# CloudCover.net
KiCad netlist of a schematic drawn in Altium Designer
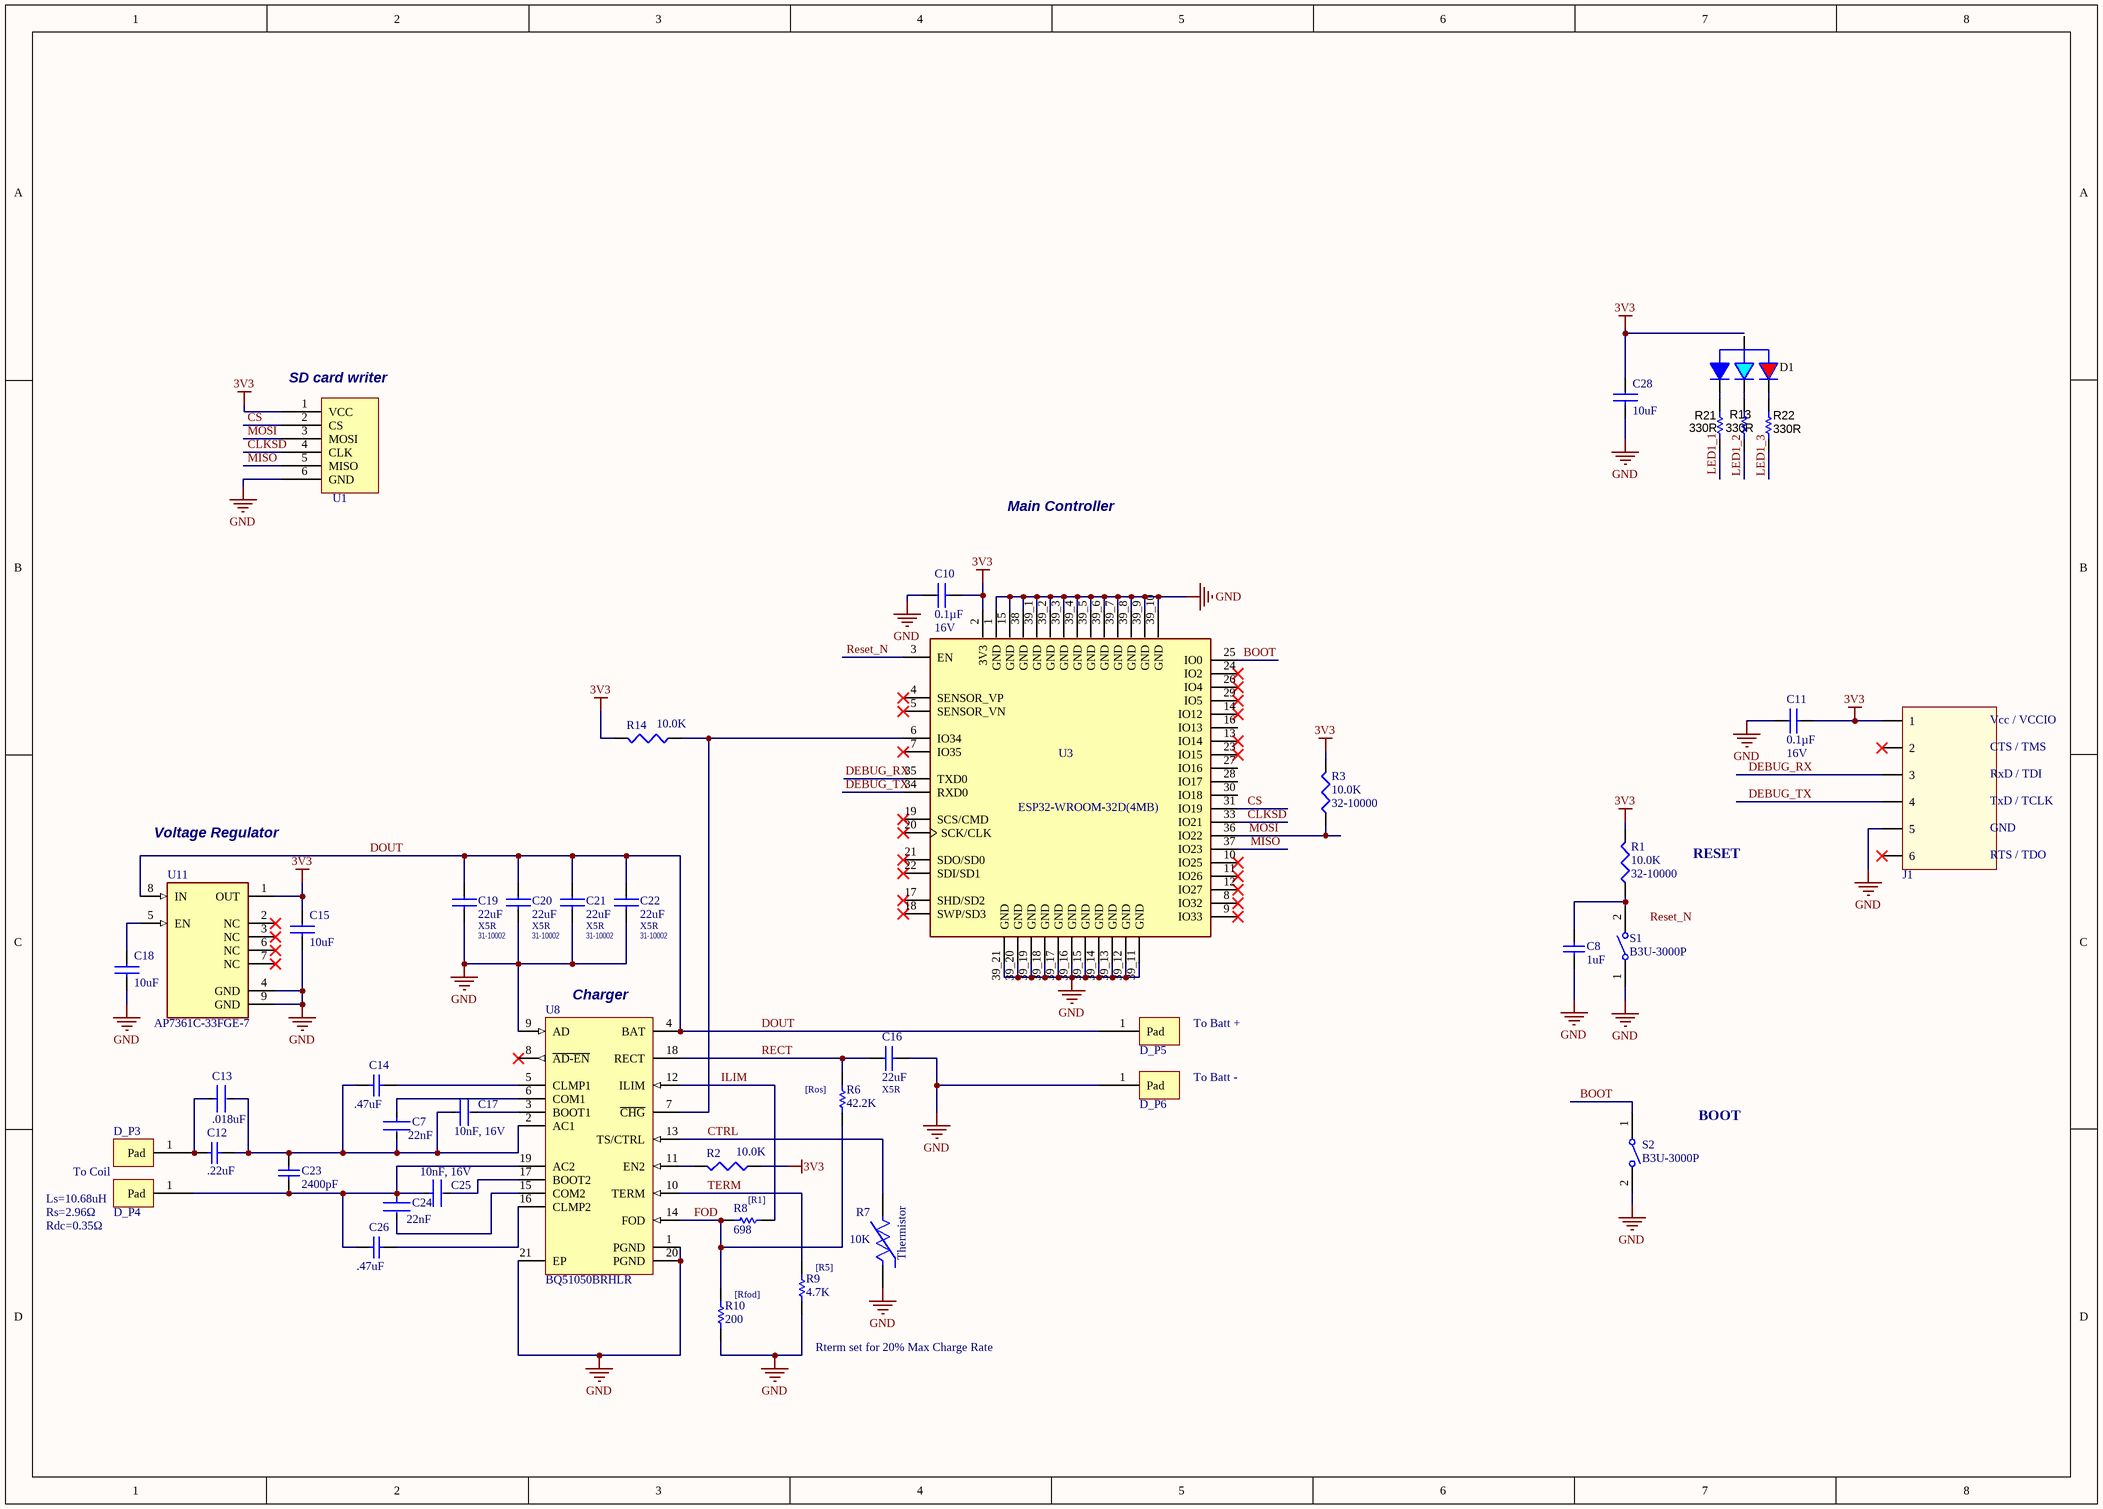
[diagram p0: CloudCover.SchDoc]

(export (version "E")
  (design (tool "Eeschema 10.0.6"))
  (components
    (comp (ref "C7")
      (value "22nF")
      (footprint "FP-CC0402-MFG")
      (description "CC0402KPX7R7BB223 CC0402 22 nF X7R 10.00% 16 V")
      (fields
        (field (name "MANUFACTURER") "YAGEO")
        (field (name "OCTOPART") "https://octopart.com/cc0402kpx7r7bb223-yageo-39266182")
      )
      (libsource (lib "Altium Content Vault") (part "11868f565c42a9108669ba33697ecf6"))
    )
    (comp (ref "C8")
      (value "1uF")
      (footprint "CAPC1005X55X25LL05T10")
      (description "GRM155C80J105KE15D")
      (fields (field (name "MANUFACTURER") "Murata"))
      (libsource (lib "Altium Content Vault") (part "CAP"))
    )
    (comp (ref "C10")
      (value "Cap, 0.1uF, 16V, X7R, 0402")
      (footprint "SMC_IPC_0402")
      (description "Capacitor, Ceramic, 0402, X7R, 16V, 0.1uF")
      (fields
        (field (name "TOLERANCE") "±10%")
        (field (name "MANUFACTURER") "Murata Electronics North America")
        (field (name "CAPACITANCE") "0.1µF")
        (field (name "VOLTAGE - RATED") "16V")
      )
      (libsource (lib "Kickr Sch Lib") (part "31-10107"))
    )
    (comp (ref "C11")
      (value "Cap, 0.1uF, 16V, X7R, 0402")
      (footprint "SMC_IPC_0402")
      (description "Capacitor, Ceramic, 0402, X7R, 16V, 0.1uF")
      (fields
        (field (name "TOLERANCE") "±10%")
        (field (name "MANUFACTURER") "Murata Electronics North America")
        (field (name "CAPACITANCE") "0.1µF")
        (field (name "VOLTAGE - RATED") "16V")
      )
      (libsource (lib "Kickr Sch Lib") (part "31-10107"))
    )
    (comp (ref "C12")
      (value ".22uF")
      (footprint "CAPC2013X145X50ML20T25")
      (description "C0805C224J5RACTU")
      (fields (field (name "MANUFACTURER") "Kemet"))
      (libsource (lib "Altium Content Vault") (part "CAP"))
    )
    (comp (ref "C13")
      (value ".018uF")
      (footprint "FP-C0603C-CF-MFG")
      (description "C0603C183J5RAC7867 C0603 18,000 pF X7R 30ppm/°C 5.00% 50 V")
      (fields
        (field (name "MANUFACTURER") "KEMET")
        (field (name "OCTOPART") "https://octopart.com/c0603c183j5rac7867-kemet-1732095")
      )
      (libsource (lib "Altium Content Vault") (part "b4654b650e69147ec39a6b967a45e02"))
    )
    (comp (ref "C14")
      (value ".47uF")
      (footprint "CAPC1005X55X25LL05T10")
      (description "GRM155R60J474KE19D .47uF 0402")
      (fields (field (name "MANUFACTURER") "Murata") (field (name "PART NUMBER") "GRM155R60J474KE19D"))
      (libsource (lib "Altium Content Vault") (part "CAP"))
    )
    (comp (ref "C15")
      (value "10uF")
      (footprint "SMC_0603")
      (description "CAP CER 10UF 16V X6S 0603")
      (fields
        (field (name "MANUFACTURER") "Murata Electronics North America")
        (field (name "MANUFACTURER PART NUMBER") "GRM188C81C106MA73D")
      )
      (libsource (lib "Kickr Sch Lib") (part "31-10103"))
    )
    (comp (ref "C16")
      (value "22uF")
      (footprint "SMC_0805")
      (description "CAP CER 22UF 10V 20% X5R 0805")
      (fields
        (field (name "TOLERANCE") "20%")
        (field (name "MANUFACTURER") "TDK Corporation")
        (field (name "DIELECTRIC") "X5R")
      )
      (libsource (lib "Kickr Sch Lib") (part "31-10002"))
    )
    (comp (ref "C17")
      (value "10nF, 16V")
      (footprint "FP-CC0402-MFG")
      (description "CC0402KRX7R7BB103 CAP CER 10000PF 16V X7R 0402")
      (fields (field (name "MANUFACTURER PART NUMBER") "CC0402KRX7R7BB103") (field (name "TOLERANCE") "0.1"))
      (libsource (lib "Altium Content Vault") (part "11868f565c42a9108669ba33697ecf6"))
    )
    (comp (ref "C18")
      (value "10uF")
      (footprint "SMC_0603")
      (description "CAP CER 10UF 16V X6S 0603")
      (fields
        (field (name "MANUFACTURER") "Murata Electronics North America")
        (field (name "MANUFACTURER PART NUMBER") "GRM188C81C106MA73D")
      )
      (libsource (lib "Kickr Sch Lib") (part "31-10103"))
    )
    (comp (ref "C19")
      (value "22uF")
      (footprint "SMC_0805")
      (description "CAP CER 22UF 10V 20% X5R 0805")
      (fields
        (field (name "TOLERANCE") "20%")
        (field (name "MANUFACTURER") "TDK Corporation")
        (field (name "DIELECTRIC") "X5R")
        (field (name "INNOVOLT PART NUMBER") "31-10002")
      )
      (libsource (lib "Kickr Sch Lib") (part "31-10002"))
    )
    (comp (ref "C20")
      (value "22uF")
      (footprint "SMC_0805")
      (description "CAP CER 22UF 10V 20% X5R 0805")
      (fields
        (field (name "TOLERANCE") "20%")
        (field (name "MANUFACTURER") "TDK Corporation")
        (field (name "DIELECTRIC") "X5R")
        (field (name "INNOVOLT PART NUMBER") "31-10002")
      )
      (libsource (lib "Kickr Sch Lib") (part "31-10002"))
    )
    (comp (ref "C21")
      (value "22uF")
      (footprint "SMC_0805")
      (description "CAP CER 22UF 10V 20% X5R 0805")
      (fields
        (field (name "TOLERANCE") "20%")
        (field (name "MANUFACTURER") "TDK Corporation")
        (field (name "DIELECTRIC") "X5R")
        (field (name "INNOVOLT PART NUMBER") "31-10002")
      )
      (libsource (lib "Kickr Sch Lib") (part "31-10002"))
    )
    (comp (ref "C22")
      (value "22uF")
      (footprint "SMC_0805")
      (description "CAP CER 22UF 10V 20% X5R 0805")
      (fields
        (field (name "TOLERANCE") "20%")
        (field (name "MANUFACTURER") "TDK Corporation")
        (field (name "DIELECTRIC") "X5R")
        (field (name "INNOVOLT PART NUMBER") "31-10002")
      )
      (libsource (lib "Kickr Sch Lib") (part "31-10002"))
    )
    (comp (ref "C23")
      (value "2400pF")
      (footprint "CAPC1608X90X35NL10T15")
      (description "GRM1885C1H242JA01D")
      (fields (field (name "MANUFACTURER") "Murata"))
      (libsource (lib "Altium Content Vault") (part "CAP"))
    )
    (comp (ref "C24")
      (value "22nF")
      (footprint "FP-CC0402-MFG")
      (description "CC0402KPX7R7BB223 CC0402 22 nF X7R 10.00% 16 V")
      (fields
        (field (name "MANUFACTURER") "YAGEO")
        (field (name "OCTOPART") "https://octopart.com/cc0402kpx7r7bb223-yageo-39266182")
      )
      (libsource (lib "Altium Content Vault") (part "11868f565c42a9108669ba33697ecf6"))
    )
    (comp (ref "C25")
      (value "10nF, 16V")
      (footprint "FP-CC0402-MFG")
      (description "CC0402KRX7R7BB103 CAP CER 10000PF 16V X7R 0402")
      (fields (field (name "MANUFACTURER PART NUMBER") "CC0402KRX7R7BB103") (field (name "TOLERANCE") "0.1"))
      (libsource (lib "Altium Content Vault") (part "11868f565c42a9108669ba33697ecf6"))
    )
    (comp (ref "C26")
      (value ".47uF")
      (footprint "CAPC1005X55X25LL05T10")
      (description "GRM155R60J474KE19D .47uF 0402")
      (fields (field (name "MANUFACTURER") "Murata") (field (name "PART NUMBER") "GRM155R60J474KE19D"))
      (libsource (lib "Altium Content Vault") (part "CAP"))
    )
    (comp (ref "C28")
      (value "10uF")
      (footprint "SMC_0603")
      (description "CAP CER 10UF 16V X6S 0603")
      (fields
        (field (name "MANUFACTURER") "Murata Electronics North America")
        (field (name "MANUFACTURER PART NUMBER") "GRM188C81C106MA73D")
      )
      (libsource (lib "Kickr Sch Lib") (part "31-10103"))
    )
    (comp (ref "D1")
      (value "CLMVC-FKC-CGJJM569ABB7A343")
      (footprint "CLMVC-FKC-CGJJM569ABB7A343")
      (description "LED Multicolor Red/Green/Blue 624nm/540nm/470nm 25mA/13mA/13mA 4-Pin Surface Mount T/R")
      (fields (field (name "MANUFACTURER") "Cree"))
      (libsource (lib "FAMIS") (part "CLMVC-FKC-CGJJM569ABB7A343"))
    )
    (comp (ref "D_P3") (value "PAD") (footprint "PAD 2x1.5") (libsource (lib "") (part "PAD_1_1")))
    (comp (ref "D_P4") (value "PAD") (footprint "PAD 2x1.5") (libsource (lib "") (part "PAD_1_1")))
    (comp (ref "D_P5") (value "PAD") (footprint "PAD 2x1.5") (libsource (lib "Kickr Sch Lib") (part "PAD_1")))
    (comp (ref "D_P6") (value "PAD") (footprint "PAD 2x1.5") (libsource (lib "Kickr Sch Lib") (part "PAD_1")))
    (comp (ref "J1")
      (value "TC2030-NL-FTDI TTL-232R USB")
      (footprint "TC2030-MCP - NL")
      (description "Footprint TC2030-CTX Debug Connector")
      (fields (field (name "INNOVOLT PART NUMBER") "40-10067") (field (name "MANUFACTURER") "Tag-Connect"))
      (libsource (lib "SudHub") (part "TC2030-NL"))
    )
    (comp (ref "R1")
      (value "10.0K")
      (footprint "SMR_0402 - Basil")
      (description "RES 10.0K OHM 1/16W 1% 0402 SMD")
      (fields
        (field (name "MANUFACTURER PART NUMBER") "RC0402FR-0710KL")
        (field (name "MANUFACTURER") "Yageo")
        (field (name "INNOVOLT PART NUMBER") "32-10000")
      )
      (libsource (lib "Kickr Sch Lib") (part "32-10000"))
    )
    (comp (ref "R2")
      (value "10.0K")
      (footprint "SMR_0402 - Basil")
      (description "RES 10.0K OHM 1/16W 1% 0402 SMD")
      (fields
        (field (name "MANUFACTURER PART NUMBER") "RC0402FR-0710KL")
        (field (name "MANUFACTURER") "Yageo")
      )
      (libsource (lib "Kickr Sch Lib") (part "32-10000"))
    )
    (comp (ref "R3")
      (value "10.0K")
      (footprint "SMR_0402 - Basil")
      (description "RES 10.0K OHM 1/16W 1% 0402 SMD")
      (fields
        (field (name "MANUFACTURER PART NUMBER") "RC0402FR-0710KL")
        (field (name "MANUFACTURER") "Yageo")
        (field (name "INNOVOLT PART NUMBER") "32-10000")
      )
      (libsource (lib "Kickr Sch Lib") (part "32-10000"))
    )
    (comp (ref "R6")
      (value "42.2K")
      (footprint "RESC1005X40X25NL05T10")
      (description "RC0402FR-0742K2L 42.2K, 1/16W, 0402")
      (fields (field (name "PART NUMBER") "RC0402FR-0742K2L") (field (name "MANUFACTURER") "Yageo / Phycomp"))
      (libsource (lib "Altium Content Vault") (part "RES"))
    )
    (comp (ref "R7")
      (value "10K")
      (footprint "FP-NTCS0805-MFG")
      (description "B57863S0103F040")
      (fields
        (field (name "OCTOPART") "https://octopart.com/ntcs0805e3103jmt-vishay-39723061")
        (field (name "TOLERANCE") "5%")
      )
      (libsource (lib "Altium Content Vault") (part "3b148a6ebabc5fb4d708a66c052d352"))
    )
    (comp (ref "R8")
      (value "698")
      (footprint "RESC1005X40X25ML05T05")
      (description "CRCW0402698RFKED 698 ohm, 1/16W, 0402")
      (fields (field (name "MANUFACTURER") "Vishay Dale") (field (name "PART NUMBER") "CRCW0402698RFKED"))
      (libsource (lib "Altium Content Vault") (part "RES"))
    )
    (comp (ref "R9")
      (value "4.7K")
      (footprint "RESC1005X40X25LL05T05")
      (fields (field (name "TOLERANCE") "1%") (field (name "PARTNUMBER") "ERJ-2RKF4701X"))
      (libsource (lib "Altium Content Vault") (part "RES-2"))
    )
    (comp (ref "R10")
      (value "200")
      (footprint "RESC1005X40X25ML05T10")
      (description "RC0402FR-07200RL 200 ohm, 1/16W, 0402")
      (fields (field (name "MANUFACTURER") "Yageo / Phycomp") (field (name "PART NUMBER") "RC0402FR-07200RL"))
      (libsource (lib "Altium Content Vault") (part "RES"))
    )
    (comp (ref "R13")
      (value "330R")
      (footprint "0402")
      (description "Res Thick Film 0402 330 Ohm 1% 1/16W ±100ppm/°C Molded SMD Paper T/R")
      (fields
        (field (name "MANUFACTURER") "Vishay")
        (field (name "MANUFACTURER PART NUMBER") "CRCW0402330RFKED")
      )
      (libsource (lib "FAMIS") (part "CRCW0402330RFKED"))
    )
    (comp (ref "R14")
      (value "10.0K")
      (footprint "SMR_0402 - Basil")
      (description "RES 10.0K OHM 1/16W 1% 0402 SMD")
      (fields
        (field (name "MANUFACTURER PART NUMBER") "RC0402FR-0710KL")
        (field (name "MANUFACTURER") "Yageo")
      )
      (libsource (lib "Kickr Sch Lib") (part "32-10000"))
    )
    (comp (ref "R21")
      (value "330R")
      (footprint "0402")
      (description "Res Thick Film 0402 330 Ohm 1% 1/16W ±100ppm/°C Molded SMD Paper T/R")
      (fields
        (field (name "MANUFACTURER") "Vishay")
        (field (name "MANUFACTURER PART NUMBER") "CRCW0402330RFKED")
      )
      (libsource (lib "FAMIS") (part "CRCW0402330RFKED"))
    )
    (comp (ref "R22")
      (value "330R")
      (footprint "0402")
      (description "Res Thick Film 0402 330 Ohm 1% 1/16W ±100ppm/°C Molded SMD Paper T/R")
      (fields
        (field (name "MANUFACTURER") "Vishay")
        (field (name "MANUFACTURER PART NUMBER") "CRCW0402330RFKED")
      )
      (libsource (lib "FAMIS") (part "CRCW0402330RFKED"))
    )
    (comp (ref "S1")
      (value "B3U-3000P")
      (footprint "OMRON-B3U-3000P_V")
      (description "Ultra-Small Tactile Switch, 1 to 50 mA, 3 to 12 V, -25 to 70 degC, 2-Pin SMD, RoHS, Tape and Reel")
      (fields (field (name "TOLERANCE") "20%"))
      (libsource (lib "Altium Content Vault") (part "SW-SPST-2_B"))
    )
    (comp (ref "S2")
      (value "B3U-3000P")
      (footprint "OMRON-B3U-3000P_V")
      (description "Ultra-Small Tactile Switch, 1 to 50 mA, 3 to 12 V, -25 to 70 degC, 2-Pin SMD, RoHS, Tape and Reel")
      (fields (field (name "TOLERANCE") "20%"))
      (libsource (lib "Altium Content Vault") (part "SW-SPST-2_B"))
    )
    (comp (ref "U1") (value "SDCARDSLOT") (libsource (lib "FAMIS") (part "SDCARDSLOT")))
    (comp (ref "U3")
      (value "ESP32-WROOM-32D(4MB)")
      (footprint "MODULE_ESP32-WROOM-32D")
      (description "Bluetooth and Wi-Fi Module 2.4GHz to 2.5GHz 2.7V to 3.6V 4MB Flash 38-Pin SMD Module")
      (fields (field (name "MANUFACTURER") "Espressif Systems"))
      (libsource (lib "FAMIS") (part "ESP32-WROOM-32D(4MB)"))
    )
    (comp (ref "U8")
      (value "BQ51050BRHLR")
      (footprint "RHL0020A_V")
      (libsource (lib "Altium Content Vault") (part "TI-BQ51050B_51051B-RHL20"))
    )
    (comp (ref "U11")
      (value "AP7361C-33FGE-7")
      (footprint "FP-U-DFN3030-8_Type_E-MFG")
      (description "IC REG LINEAR 3.3V 1A UDFN3030-8")
      (fields
        (field (name "MANUFACTURER") "Diodes Inc.")
        (field (name "OCTOPART") "https://octopart.com/ap7361c-33fge-7-diodes+inc.-65869522")
      )
      (libsource (lib "Altium Content Vault") (part "2971fe8480f7e8815ea3c3920f93e3e"))
    )
  )
  (nets
    (net (code "1") (name "/BOOT") (class "Default")
      (node (ref "S2") (pin "1") (pinfunction "1_1") (pintype "passive"))
      (node (ref "U3") (pin "25") (pinfunction "IO0_25") (pintype "passive"))
    )
    (net (code "2") (name "/CLKSD") (class "Default")
      (node (ref "U1") (pin "4") (pinfunction "CLK_4") (pintype "passive"))
      (node (ref "U3") (pin "33") (pinfunction "IO21_33") (pintype "passive"))
    )
    (net (code "3") (name "/CS") (class "Default")
      (node (ref "U1") (pin "2") (pinfunction "CS_2") (pintype "passive"))
      (node (ref "U3") (pin "31") (pinfunction "IO19_31") (pintype "passive"))
    )
    (net (code "4") (name "/CTRL") (class "Default")
      (node (ref "R7") (pin "2") (pinfunction "2_2") (pintype "passive"))
      (node (ref "U8") (pin "13") (pinfunction "TS/CTRL_13") (pintype "input"))
    )
    (net (code "5") (name "/DEBUG_RX") (class "Default")
      (node (ref "J1") (pin "3") (pinfunction "3_3") (pintype "passive"))
      (node (ref "U3") (pin "35") (pinfunction "TXD0_35") (pintype "passive"))
    )
    (net (code "6") (name "/DEBUG_TX") (class "Default")
      (node (ref "J1") (pin "4") (pinfunction "4_4") (pintype "passive"))
      (node (ref "U3") (pin "34") (pinfunction "RXD0_34") (pintype "passive"))
    )
    (net (code "7") (name "/DOUT") (class "Default")
      (node (ref "C19") (pin "1") (pinfunction "1_1") (pintype "passive"))
      (node (ref "C20") (pin "1") (pinfunction "1_1") (pintype "passive"))
      (node (ref "C21") (pin "1") (pinfunction "1_1") (pintype "passive"))
      (node (ref "C22") (pin "1") (pinfunction "1_1") (pintype "passive"))
      (node (ref "D_P5") (pin "1") (pinfunction "Pad_1") (pintype "passive"))
      (node (ref "U11") (pin "8") (pinfunction "IN_8") (pintype "input"))
      (node (ref "U8") (pin "4") (pinfunction "BAT_4") (pintype "power_in"))
    )
    (net (code "8") (name "/FOD") (class "Default")
      (node (ref "R10") (pin "2") (pinfunction "2_2") (pintype "passive"))
      (node (ref "R6") (pin "1") (pinfunction "1_1") (pintype "passive"))
      (node (ref "R8") (pin "1") (pinfunction "1_1") (pintype "passive"))
      (node (ref "U8") (pin "14") (pinfunction "FOD_14") (pintype "input"))
    )
    (net (code "9") (name "/ILIM") (class "Default")
      (node (ref "R8") (pin "2") (pinfunction "2_2") (pintype "passive"))
      (node (ref "U8") (pin "12") (pinfunction "ILIM_12") (pintype "input"))
    )
    (net (code "10") (name "/LED1_1") (class "Default")
      (node (ref "R21") (pin "1") (pinfunction "1_1") (pintype "passive"))
    )
    (net (code "11") (name "/LED1_2") (class "Default")
      (node (ref "R13") (pin "1") (pinfunction "1_1") (pintype "passive"))
    )
    (net (code "12") (name "/LED1_3") (class "Default")
      (node (ref "R22") (pin "1") (pinfunction "1_1") (pintype "passive"))
    )
    (net (code "13") (name "/MISO") (class "Default")
      (node (ref "U1") (pin "5") (pinfunction "MISO_5") (pintype "passive"))
      (node (ref "U3") (pin "37") (pinfunction "IO23_37") (pintype "passive"))
    )
    (net (code "14") (name "/MOSI") (class "Default")
      (node (ref "R3") (pin "1") (pinfunction "1_1") (pintype "passive"))
      (node (ref "U1") (pin "3") (pinfunction "MOSI_3") (pintype "passive"))
      (node (ref "U3") (pin "36") (pinfunction "IO22_36") (pintype "passive"))
    )
    (net (code "15") (name "/RECT") (class "Default")
      (node (ref "C16") (pin "1") (pinfunction "1_1") (pintype "passive"))
      (node (ref "R6") (pin "2") (pinfunction "2_2") (pintype "passive"))
      (node (ref "U8") (pin "18") (pinfunction "RECT_18") (pintype "passive"))
    )
    (net (code "16") (name "/Reset_N") (class "Default")
      (node (ref "U3") (pin "3") (pinfunction "EN_3") (pintype "passive"))
    )
    (net (code "17") (name "/TERM") (class "Default")
      (node (ref "R9") (pin "2") (pinfunction "2_2") (pintype "passive"))
      (node (ref "U8") (pin "10") (pinfunction "TERM_10") (pintype "input"))
    )
    (net (code "18") (name "3V3") (class "Default")
      (node (ref "C10") (pin "2") (pinfunction "2_2") (pintype "passive"))
      (node (ref "C11") (pin "2") (pinfunction "2_2") (pintype "passive"))
      (node (ref "C15") (pin "1") (pinfunction "1_1") (pintype "passive"))
      (node (ref "C28") (pin "1") (pinfunction "1_1") (pintype "passive"))
      (node (ref "J1") (pin "1") (pinfunction "1_1") (pintype "passive"))
      (node (ref "R1") (pin "2") (pinfunction "2_2") (pintype "passive"))
      (node (ref "R14") (pin "2") (pinfunction "2_2") (pintype "passive"))
      (node (ref "R2") (pin "1") (pinfunction "1_1") (pintype "passive"))
      (node (ref "R3") (pin "2") (pinfunction "2_2") (pintype "passive"))
      (node (ref "U1") (pin "1") (pinfunction "VCC_1") (pintype "passive"))
      (node (ref "U11") (pin "1") (pinfunction "OUT_1") (pintype "power_in"))
      (node (ref "U3") (pin "2") (pinfunction "3V3_2") (pintype "passive"))
    )
    (net (code "19") (name "GND") (class "Default")
      (node (ref "C10") (pin "1") (pinfunction "1_1") (pintype "passive"))
      (node (ref "C11") (pin "1") (pinfunction "1_1") (pintype "passive"))
      (node (ref "C15") (pin "2") (pinfunction "2_2") (pintype "passive"))
      (node (ref "C16") (pin "2") (pinfunction "2_2") (pintype "passive"))
      (node (ref "C18") (pin "2") (pinfunction "2_2") (pintype "passive"))
      (node (ref "C19") (pin "2") (pinfunction "2_2") (pintype "passive"))
      (node (ref "C20") (pin "2") (pinfunction "2_2") (pintype "passive"))
      (node (ref "C21") (pin "2") (pinfunction "2_2") (pintype "passive"))
      (node (ref "C22") (pin "2") (pinfunction "2_2") (pintype "passive"))
      (node (ref "C28") (pin "2") (pinfunction "2_2") (pintype "passive"))
      (node (ref "C8") (pin "1") (pinfunction "1_1") (pintype "passive"))
      (node (ref "D_P6") (pin "1") (pinfunction "Pad_1") (pintype "passive"))
      (node (ref "J1") (pin "5") (pinfunction "5_5") (pintype "passive"))
      (node (ref "R10") (pin "1") (pinfunction "1_1") (pintype "passive"))
      (node (ref "R7") (pin "1") (pinfunction "1_1") (pintype "passive"))
      (node (ref "R9") (pin "1") (pinfunction "1_1") (pintype "passive"))
      (node (ref "S1") (pin "1") (pinfunction "1_1") (pintype "passive"))
      (node (ref "S2") (pin "2") (pinfunction "2_2") (pintype "passive"))
      (node (ref "U1") (pin "6") (pinfunction "GND_6") (pintype "passive"))
      (node (ref "U11") (pin "4") (pinfunction "GND_4") (pintype "power_in"))
      (node (ref "U11") (pin "9") (pinfunction "GND_9") (pintype "power_in"))
      (node (ref "U3") (pin "1") (pinfunction "GND_1") (pintype "passive"))
      (node (ref "U3") (pin "15") (pinfunction "GND_15") (pintype "passive"))
      (node (ref "U3") (pin "38") (pinfunction "GND_38") (pintype "passive"))
      (node (ref "U3") (pin "39_1") (pinfunction "GND_39_1") (pintype "passive"))
      (node (ref "U3") (pin "39_10") (pinfunction "GND_39_10") (pintype "passive"))
      (node (ref "U3") (pin "39_11") (pinfunction "GND_39_11") (pintype "passive"))
      (node (ref "U3") (pin "39_12") (pinfunction "GND_39_12") (pintype "passive"))
      (node (ref "U3") (pin "39_13") (pinfunction "GND_39_13") (pintype "passive"))
      (node (ref "U3") (pin "39_14") (pinfunction "GND_39_14") (pintype "passive"))
      (node (ref "U3") (pin "39_15") (pinfunction "GND_39_15") (pintype "passive"))
      (node (ref "U3") (pin "39_16") (pinfunction "GND_39_16") (pintype "passive"))
      (node (ref "U3") (pin "39_17") (pinfunction "GND_39_17") (pintype "passive"))
      (node (ref "U3") (pin "39_18") (pinfunction "GND_39_18") (pintype "passive"))
      (node (ref "U3") (pin "39_19") (pinfunction "GND_39_19") (pintype "passive"))
      (node (ref "U3") (pin "39_2") (pinfunction "GND_39_2") (pintype "passive"))
      (node (ref "U3") (pin "39_20") (pinfunction "GND_39_20") (pintype "passive"))
      (node (ref "U3") (pin "39_21") (pinfunction "GND_39_21") (pintype "passive"))
      (node (ref "U3") (pin "39_3") (pinfunction "GND_39_3") (pintype "passive"))
      (node (ref "U3") (pin "39_4") (pinfunction "GND_39_4") (pintype "passive"))
      (node (ref "U3") (pin "39_5") (pinfunction "GND_39_5") (pintype "passive"))
      (node (ref "U3") (pin "39_6") (pinfunction "GND_39_6") (pintype "passive"))
      (node (ref "U3") (pin "39_7") (pinfunction "GND_39_7") (pintype "passive"))
      (node (ref "U3") (pin "39_8") (pinfunction "GND_39_8") (pintype "passive"))
      (node (ref "U3") (pin "39_9") (pinfunction "GND_39_9") (pintype "passive"))
      (node (ref "U8") (pin "1") (pinfunction "PGND_1") (pintype "power_in"))
      (node (ref "U8") (pin "20") (pinfunction "PGND_20") (pintype "power_in"))
      (node (ref "U8") (pin "21") (pinfunction "EP_21") (pintype "passive"))
      (node (ref "U8") (pin "9") (pinfunction "AD_9") (pintype "input"))
    )
    (net (code "20") (name "Net-(C8-Pad2)") (class "Default")
      (node (ref "C8") (pin "2") (pinfunction "2_2") (pintype "passive"))
      (node (ref "R1") (pin "1") (pinfunction "1_1") (pintype "passive"))
      (node (ref "S1") (pin "2") (pinfunction "2_2") (pintype "passive"))
    )
    (net (code "21") (name "Net-(C12-Pad1)") (class "Default")
      (node (ref "C12") (pin "1") (pinfunction "1_1") (pintype "passive"))
      (node (ref "C13") (pin "1") (pinfunction "1_1") (pintype "passive"))
      (node (ref "D_P3") (pin "1") (pinfunction "Pad_1") (pintype "passive"))
    )
    (net (code "22") (name "Net-(D1-K-Pad2)") (class "Default")
      (node (ref "D1") (pin "2") (pinfunction "K_2") (pintype "passive"))
      (node (ref "R21") (pin "2") (pinfunction "2_2") (pintype "passive"))
    )
    (net (code "23") (name "Net-(D1-K-Pad3)") (class "Default")
      (node (ref "D1") (pin "3") (pinfunction "K_3") (pintype "passive"))
      (node (ref "R13") (pin "2") (pinfunction "2_2") (pintype "passive"))
    )
    (net (code "24") (name "Net-(D1-K-Pad4)") (class "Default")
      (node (ref "D1") (pin "4") (pinfunction "K_4") (pintype "passive"))
      (node (ref "R22") (pin "2") (pinfunction "2_2") (pintype "passive"))
    )
    (net (code "25") (name "Net-(U3-IO34)") (class "Default")
      (node (ref "R14") (pin "1") (pinfunction "1_1") (pintype "passive"))
      (node (ref "U3") (pin "6") (pinfunction "IO34_6") (pintype "passive"))
      (node (ref "U8") (pin "7") (pinfunction "~{CHG}_7") (pintype "open_collector"))
    )
    (net (code "26") (name "Net-(U8-AC1)") (class "Default")
      (node (ref "C12") (pin "2") (pinfunction "2_2") (pintype "passive"))
      (node (ref "C13") (pin "2") (pinfunction "2_2") (pintype "passive"))
      (node (ref "C14") (pin "1") (pinfunction "1_1") (pintype "passive"))
      (node (ref "C17") (pin "1") (pinfunction "1_1") (pintype "passive"))
      (node (ref "C23") (pin "2") (pinfunction "2_2") (pintype "passive"))
      (node (ref "C7") (pin "2") (pinfunction "2_2") (pintype "passive"))
      (node (ref "U8") (pin "2") (pinfunction "AC1_2") (pintype "power_in"))
    )
    (net (code "27") (name "Net-(U8-AC2)") (class "Default")
      (node (ref "C23") (pin "1") (pinfunction "1_1") (pintype "passive"))
      (node (ref "C24") (pin "1") (pinfunction "1_1") (pintype "passive"))
      (node (ref "C25") (pin "1") (pinfunction "1_1") (pintype "passive"))
      (node (ref "C26") (pin "1") (pinfunction "1_1") (pintype "passive"))
      (node (ref "D_P4") (pin "1") (pinfunction "Pad_1") (pintype "passive"))
      (node (ref "U8") (pin "19") (pinfunction "AC2_19") (pintype "power_in"))
    )
    (net (code "28") (name "Net-(U8-BOOT1)") (class "Default")
      (node (ref "C17") (pin "2") (pinfunction "2_2") (pintype "passive"))
      (node (ref "U8") (pin "3") (pinfunction "BOOT1_3") (pintype "passive"))
    )
    (net (code "29") (name "Net-(U8-BOOT2)") (class "Default")
      (node (ref "C25") (pin "2") (pinfunction "2_2") (pintype "passive"))
      (node (ref "U8") (pin "17") (pinfunction "BOOT2_17") (pintype "passive"))
    )
    (net (code "30") (name "Net-(U8-CLMP1)") (class "Default")
      (node (ref "C14") (pin "2") (pinfunction "2_2") (pintype "passive"))
      (node (ref "U8") (pin "5") (pinfunction "CLMP1_5") (pintype "open_collector"))
    )
    (net (code "31") (name "Net-(U8-CLMP2)") (class "Default")
      (node (ref "C26") (pin "2") (pinfunction "2_2") (pintype "passive"))
      (node (ref "U8") (pin "16") (pinfunction "CLMP2_16") (pintype "open_collector"))
    )
    (net (code "32") (name "Net-(U8-COM1)") (class "Default")
      (node (ref "C7") (pin "1") (pinfunction "1_1") (pintype "passive"))
      (node (ref "U8") (pin "6") (pinfunction "COM1_6") (pintype "open_collector"))
    )
    (net (code "33") (name "Net-(U8-COM2)") (class "Default")
      (node (ref "C24") (pin "2") (pinfunction "2_2") (pintype "passive"))
      (node (ref "U8") (pin "15") (pinfunction "COM2_15") (pintype "open_collector"))
    )
    (net (code "34") (name "Net-(U8-EN2)") (class "Default")
      (node (ref "R2") (pin "2") (pinfunction "2_2") (pintype "passive"))
      (node (ref "U8") (pin "11") (pinfunction "EN2_11") (pintype "input"))
    )
    (net (code "35") (name "Net-(U11-EN)") (class "Default")
      (node (ref "C18") (pin "1") (pinfunction "1_1") (pintype "passive"))
      (node (ref "U11") (pin "5") (pinfunction "EN_5") (pintype "input"))
    )
    (net (code "36") (name "unconnected-(D1-A-Pad1)") (class "Default")
      (node (ref "D1") (pin "1") (pinfunction "A_1") (pintype "passive"))
    )
    (net (code "37") (name "unconnected-(J1-Pad2)") (class "Default")
      (node (ref "J1") (pin "2") (pinfunction "2_2") (pintype "passive+no_connect"))
    )
    (net (code "38") (name "unconnected-(J1-Pad6)") (class "Default")
      (node (ref "J1") (pin "6") (pinfunction "6_6") (pintype "passive+no_connect"))
    )
    (net (code "39") (name "unconnected-(U3-IO2-Pad24)") (class "Default")
      (node (ref "U3") (pin "24") (pinfunction "IO2_24") (pintype "passive+no_connect"))
    )
    (net (code "40") (name "unconnected-(U3-IO4-Pad26)") (class "Default")
      (node (ref "U3") (pin "26") (pinfunction "IO4_26") (pintype "passive+no_connect"))
    )
    (net (code "41") (name "unconnected-(U3-IO5-Pad29)") (class "Default")
      (node (ref "U3") (pin "29") (pinfunction "IO5_29") (pintype "passive+no_connect"))
    )
    (net (code "42") (name "unconnected-(U3-IO12-Pad14)") (class "Default")
      (node (ref "U3") (pin "14") (pinfunction "IO12_14") (pintype "passive+no_connect"))
    )
    (net (code "43") (name "unconnected-(U3-IO13-Pad16)") (class "Default")
      (node (ref "U3") (pin "16") (pinfunction "IO13_16") (pintype "passive"))
    )
    (net (code "44") (name "unconnected-(U3-IO14-Pad13)") (class "Default")
      (node (ref "U3") (pin "13") (pinfunction "IO14_13") (pintype "passive+no_connect"))
    )
    (net (code "45") (name "unconnected-(U3-IO15-Pad23)") (class "Default")
      (node (ref "U3") (pin "23") (pinfunction "IO15_23") (pintype "passive+no_connect"))
    )
    (net (code "46") (name "unconnected-(U3-IO16-Pad27)") (class "Default")
      (node (ref "U3") (pin "27") (pinfunction "IO16_27") (pintype "passive"))
    )
    (net (code "47") (name "unconnected-(U3-IO17-Pad28)") (class "Default")
      (node (ref "U3") (pin "28") (pinfunction "IO17_28") (pintype "passive"))
    )
    (net (code "48") (name "unconnected-(U3-IO18-Pad30)") (class "Default")
      (node (ref "U3") (pin "30") (pinfunction "IO18_30") (pintype "passive"))
    )
    (net (code "49") (name "unconnected-(U3-IO25-Pad10)") (class "Default")
      (node (ref "U3") (pin "10") (pinfunction "IO25_10") (pintype "passive+no_connect"))
    )
    (net (code "50") (name "unconnected-(U3-IO26-Pad11)") (class "Default")
      (node (ref "U3") (pin "11") (pinfunction "IO26_11") (pintype "passive+no_connect"))
    )
    (net (code "51") (name "unconnected-(U3-IO27-Pad12)") (class "Default")
      (node (ref "U3") (pin "12") (pinfunction "IO27_12") (pintype "passive+no_connect"))
    )
    (net (code "52") (name "unconnected-(U3-IO32-Pad8)") (class "Default")
      (node (ref "U3") (pin "8") (pinfunction "IO32_8") (pintype "passive+no_connect"))
    )
    (net (code "53") (name "unconnected-(U3-IO33-Pad9)") (class "Default")
      (node (ref "U3") (pin "9") (pinfunction "IO33_9") (pintype "passive+no_connect"))
    )
    (net (code "54") (name "unconnected-(U3-IO35-Pad7)") (class "Default")
      (node (ref "U3") (pin "7") (pinfunction "IO35_7") (pintype "passive+no_connect"))
    )
    (net (code "55") (name "unconnected-(U3-SCK{slash}CLK-Pad20)") (class "Default")
      (node (ref "U3") (pin "20") (pinfunction "SCK/CLK_20") (pintype "passive+no_connect"))
    )
    (net (code "56") (name "unconnected-(U3-SCS{slash}CMD-Pad19)") (class "Default")
      (node (ref "U3") (pin "19") (pinfunction "SCS/CMD_19") (pintype "passive+no_connect"))
    )
    (net (code "57") (name "unconnected-(U3-SDI{slash}SD1-Pad22)") (class "Default")
      (node (ref "U3") (pin "22") (pinfunction "SDI/SD1_22") (pintype "passive+no_connect"))
    )
    (net (code "58") (name "unconnected-(U3-SDO{slash}SD0-Pad21)") (class "Default")
      (node (ref "U3") (pin "21") (pinfunction "SDO/SD0_21") (pintype "passive+no_connect"))
    )
    (net (code "59") (name "unconnected-(U3-SENSOR_VN-Pad5)") (class "Default")
      (node (ref "U3") (pin "5") (pinfunction "SENSOR_VN_5") (pintype "passive+no_connect"))
    )
    (net (code "60") (name "unconnected-(U3-SENSOR_VP-Pad4)") (class "Default")
      (node (ref "U3") (pin "4") (pinfunction "SENSOR_VP_4") (pintype "passive+no_connect"))
    )
    (net (code "61") (name "unconnected-(U3-SHD{slash}SD2-Pad17)") (class "Default")
      (node (ref "U3") (pin "17") (pinfunction "SHD/SD2_17") (pintype "passive+no_connect"))
    )
    (net (code "62") (name "unconnected-(U3-SWP{slash}SD3-Pad18)") (class "Default")
      (node (ref "U3") (pin "18") (pinfunction "SWP/SD3_18") (pintype "passive+no_connect"))
    )
    (net (code "63") (name "unconnected-(U8-~{AD-EN}-Pad8)") (class "Default")
      (node (ref "U8") (pin "8") (pinfunction "~{AD-EN}_8") (pintype "output+no_connect"))
    )
    (net (code "64") (name "unconnected-(U11-NC-Pad2)") (class "Default")
      (node (ref "U11") (pin "2") (pinfunction "NC_2") (pintype "passive+no_connect"))
    )
    (net (code "65") (name "unconnected-(U11-NC-Pad3)") (class "Default")
      (node (ref "U11") (pin "3") (pinfunction "NC_3") (pintype "passive+no_connect"))
    )
    (net (code "66") (name "unconnected-(U11-NC-Pad6)") (class "Default")
      (node (ref "U11") (pin "6") (pinfunction "NC_6") (pintype "passive+no_connect"))
    )
    (net (code "67") (name "unconnected-(U11-NC-Pad7)") (class "Default")
      (node (ref "U11") (pin "7") (pinfunction "NC_7") (pintype "passive+no_connect"))
    )
  )
)
